# FTDIAdapter.net
KiCad netlist of a schematic drawn in EAGLE
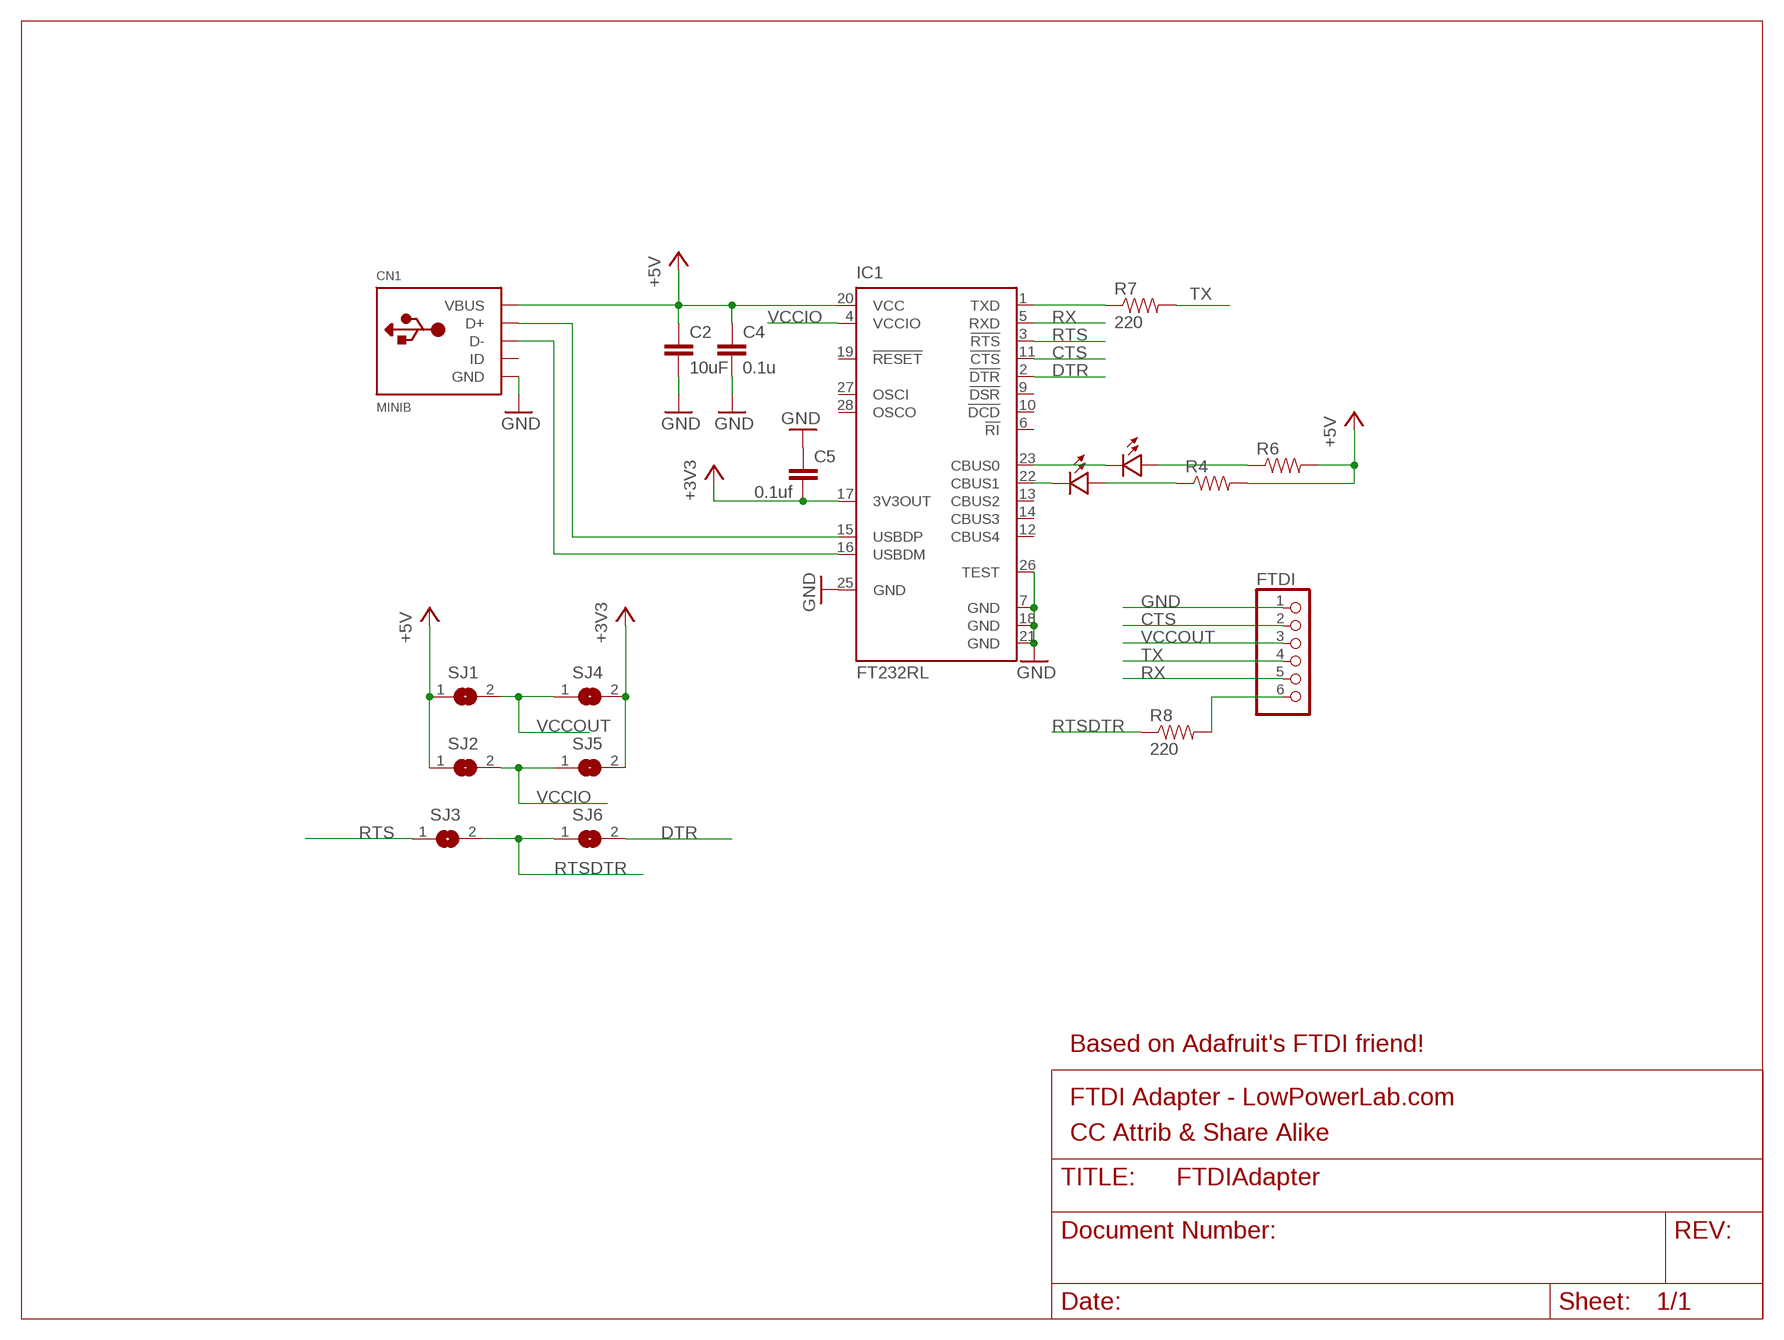
[diagram p0: schematic, sheet 1]

(export (version "E")
  (design (tool "Eeschema 10.0.6"))
  (components
    (comp (ref "C2")
      (value "10uF")
      (footprint "eagle-import:0805-CAP-LARGEPADS")
      (libsource (lib "eagle-import") (part "CAP0805-CAP-LARGEPADS"))
    )
    (comp (ref "C4")
      (value "0.1u")
      (footprint "eagle-import:0603-CAP")
      (libsource (lib "eagle-import") (part "CAP0603-CAP"))
    )
    (comp (ref "C5")
      (value "0.1uf")
      (footprint "eagle-import:0603-CAP")
      (libsource (lib "eagle-import") (part "CAP0603-CAP"))
    )
    (comp (ref "CN1")
      (value "MINIB")
      (footprint "eagle-import:USB-MINIB")
      (libsource (lib "eagle-import") (part "USBMINIB"))
    )
    (comp (ref "FTDI")
      (value "PINHD-1X6CB")
      (footprint "eagle-import:1X06-CLEANBIG")
      (libsource (lib "eagle-import") (part "PINHD-1X6CB"))
    )
    (comp (ref "IC1")
      (value "FT232RL")
      (footprint "eagle-import:SSOP28")
      (libsource (lib "eagle-import") (part "FT232RL"))
    )
    (comp (ref "R4")
      (value "RESISTOR0603-RES")
      (footprint "eagle-import:0603-RES")
      (libsource (lib "eagle-import") (part "RESISTOR0603-RES"))
    )
    (comp (ref "R6")
      (value "RESISTOR0603-RES")
      (footprint "eagle-import:0603-RES")
      (libsource (lib "eagle-import") (part "RESISTOR0603-RES"))
    )
    (comp (ref "R7")
      (value "220")
      (footprint "eagle-import:0603-RES")
      (libsource (lib "eagle-import") (part "RESISTOR0603-RES"))
    )
    (comp (ref "R8")
      (value "220")
      (footprint "eagle-import:0603-RES")
      (libsource (lib "eagle-import") (part "RESISTOR0603-RES"))
    )
    (comp (ref "SJ1") (value "SJ") (footprint "eagle-import:SJ") (libsource (lib "eagle-import") (part "SJ")))
    (comp (ref "SJ2") (value "SJ") (footprint "eagle-import:SJ") (libsource (lib "eagle-import") (part "SJ")))
    (comp (ref "SJ3") (value "SJ") (footprint "eagle-import:SJ") (libsource (lib "eagle-import") (part "SJ")))
    (comp (ref "SJ4") (value "SJ") (footprint "eagle-import:SJ") (libsource (lib "eagle-import") (part "SJ")))
    (comp (ref "SJ5") (value "SJ") (footprint "eagle-import:SJ") (libsource (lib "eagle-import") (part "SJ")))
    (comp (ref "SJ6") (value "SJ") (footprint "eagle-import:SJ") (libsource (lib "eagle-import") (part "SJ")))
    (comp (ref "U$4")
      (value "LED0603")
      (footprint "eagle-import:0603-LED")
      (libsource (lib "eagle-import") (part "LED0603"))
    )
    (comp (ref "U$5")
      (value "LED0603")
      (footprint "eagle-import:0603-LED")
      (libsource (lib "eagle-import") (part "LED0603"))
    )
  )
  (nets
    (net (code "1") (name "+3V3") (class "Default")
      (node (ref "C5") (pin "2") (pinfunction "2_2") (pintype "passive"))
      (node (ref "IC1") (pin "17") (pinfunction "3V3OUT_17") (pintype "input"))
      (node (ref "SJ4") (pin "2") (pinfunction "2_2") (pintype "passive"))
      (node (ref "SJ5") (pin "2") (pinfunction "2_2") (pintype "passive"))
    )
    (net (code "2") (name "+5V") (class "Default")
      (node (ref "C2") (pin "1") (pinfunction "1_1") (pintype "passive"))
      (node (ref "C4") (pin "1") (pinfunction "1_1") (pintype "passive"))
      (node (ref "CN1") (pin "VBUS") (pinfunction "VBUS_VBUS") (pintype "power_in"))
      (node (ref "IC1") (pin "20") (pinfunction "VCC_20") (pintype "input"))
      (node (ref "R4") (pin "2") (pinfunction "2_2") (pintype "passive"))
      (node (ref "R6") (pin "2") (pinfunction "2_2") (pintype "passive"))
      (node (ref "SJ1") (pin "1") (pinfunction "1_1") (pintype "passive"))
      (node (ref "SJ2") (pin "1") (pinfunction "1_1") (pintype "passive"))
    )
    (net (code "3") (name "/CTS") (class "Default")
      (node (ref "FTDI") (pin "2") (pinfunction "2_2") (pintype "passive"))
      (node (ref "IC1") (pin "11") (pinfunction "~{CTS}_11") (pintype "input"))
    )
    (net (code "4") (name "/DTR") (class "Default")
      (node (ref "IC1") (pin "2") (pinfunction "~{DTR}_2") (pintype "input"))
      (node (ref "SJ6") (pin "2") (pinfunction "2_2") (pintype "passive"))
    )
    (net (code "5") (name "/RTS") (class "Default")
      (node (ref "IC1") (pin "3") (pinfunction "~{RTS}_3") (pintype "input"))
      (node (ref "SJ3") (pin "1") (pinfunction "1_1") (pintype "passive"))
    )
    (net (code "6") (name "/RTSDTR") (class "Default")
      (node (ref "R8") (pin "1") (pinfunction "1_1") (pintype "passive"))
      (node (ref "SJ3") (pin "2") (pinfunction "2_2") (pintype "passive"))
      (node (ref "SJ6") (pin "1") (pinfunction "1_1") (pintype "passive"))
    )
    (net (code "7") (name "/RX") (class "Default")
      (node (ref "FTDI") (pin "5") (pinfunction "5_5") (pintype "passive"))
      (node (ref "IC1") (pin "5") (pinfunction "RXD_5") (pintype "input"))
    )
    (net (code "8") (name "/TX") (class "Default")
      (node (ref "FTDI") (pin "4") (pinfunction "4_4") (pintype "passive"))
      (node (ref "R7") (pin "2") (pinfunction "2_2") (pintype "passive"))
    )
    (net (code "9") (name "/VCCIO") (class "Default")
      (node (ref "IC1") (pin "4") (pinfunction "VCCIO_4") (pintype "input"))
      (node (ref "SJ2") (pin "2") (pinfunction "2_2") (pintype "passive"))
      (node (ref "SJ5") (pin "1") (pinfunction "1_1") (pintype "passive"))
    )
    (net (code "10") (name "/VCCOUT") (class "Default")
      (node (ref "FTDI") (pin "3") (pinfunction "3_3") (pintype "passive"))
      (node (ref "SJ1") (pin "2") (pinfunction "2_2") (pintype "passive"))
      (node (ref "SJ4") (pin "1") (pinfunction "1_1") (pintype "passive"))
    )
    (net (code "11") (name "GND") (class "Default")
      (node (ref "C2") (pin "2") (pinfunction "2_2") (pintype "passive"))
      (node (ref "C4") (pin "2") (pinfunction "2_2") (pintype "passive"))
      (node (ref "C5") (pin "1") (pinfunction "1_1") (pintype "passive"))
      (node (ref "CN1") (pin "GND") (pinfunction "GND_GND") (pintype "power_in"))
      (node (ref "FTDI") (pin "1") (pinfunction "1_1") (pintype "passive"))
      (node (ref "IC1") (pin "18") (pinfunction "GND_18") (pintype "input"))
      (node (ref "IC1") (pin "21") (pinfunction "GND_21") (pintype "input"))
      (node (ref "IC1") (pin "25") (pinfunction "GND_25") (pintype "input"))
      (node (ref "IC1") (pin "26") (pinfunction "TEST_26") (pintype "input"))
      (node (ref "IC1") (pin "7") (pinfunction "GND_7") (pintype "input"))
    )
    (net (code "12") (name "Net-(FTDI-Pad6)") (class "Default")
      (node (ref "FTDI") (pin "6") (pinfunction "6_6") (pintype "passive"))
      (node (ref "R8") (pin "2") (pinfunction "2_2") (pintype "passive"))
    )
    (net (code "13") (name "Net-(IC1-CBUS0)") (class "Default")
      (node (ref "IC1") (pin "23") (pinfunction "CBUS0_23") (pintype "input"))
      (node (ref "U$4") (pin "MINUS") (pinfunction "MINUS_MINUS") (pintype "passive"))
    )
    (net (code "14") (name "Net-(IC1-CBUS1)") (class "Default")
      (node (ref "IC1") (pin "22") (pinfunction "CBUS1_22") (pintype "input"))
      (node (ref "U$5") (pin "MINUS") (pinfunction "MINUS_MINUS") (pintype "passive"))
    )
    (net (code "15") (name "Net-(IC1-TXD)") (class "Default")
      (node (ref "IC1") (pin "1") (pinfunction "TXD_1") (pintype "input"))
      (node (ref "R7") (pin "1") (pinfunction "1_1") (pintype "passive"))
    )
    (net (code "16") (name "Net-(IC1-USBDM)") (class "Default")
      (node (ref "CN1") (pin "D-") (pinfunction "D-_D-") (pintype "bidirectional"))
      (node (ref "IC1") (pin "16") (pinfunction "USBDM_16") (pintype "input"))
    )
    (net (code "17") (name "Net-(IC1-USBDP)") (class "Default")
      (node (ref "CN1") (pin "D+") (pinfunction "D+_D+") (pintype "bidirectional"))
      (node (ref "IC1") (pin "15") (pinfunction "USBDP_15") (pintype "input"))
    )
    (net (code "18") (name "Net-(R4-Pad1)") (class "Default")
      (node (ref "R4") (pin "1") (pinfunction "1_1") (pintype "passive"))
      (node (ref "U$5") (pin "PLUS") (pinfunction "PLUS_PLUS") (pintype "passive"))
    )
    (net (code "19") (name "Net-(R6-Pad1)") (class "Default")
      (node (ref "R6") (pin "1") (pinfunction "1_1") (pintype "passive"))
      (node (ref "U$4") (pin "PLUS") (pinfunction "PLUS_PLUS") (pintype "passive"))
    )
    (net (code "20") (name "unconnected-(CN1-PadID)") (class "Default")
      (node (ref "CN1") (pin "ID") (pinfunction "ID_ID") (pintype "bidirectional"))
    )
    (net (code "21") (name "unconnected-(IC1-CBUS2-Pad13)") (class "Default")
      (node (ref "IC1") (pin "13") (pinfunction "CBUS2_13") (pintype "input"))
    )
    (net (code "22") (name "unconnected-(IC1-CBUS3-Pad14)") (class "Default")
      (node (ref "IC1") (pin "14") (pinfunction "CBUS3_14") (pintype "input"))
    )
    (net (code "23") (name "unconnected-(IC1-CBUS4-Pad12)") (class "Default")
      (node (ref "IC1") (pin "12") (pinfunction "CBUS4_12") (pintype "input"))
    )
    (net (code "24") (name "unconnected-(IC1-OSCI-Pad27)") (class "Default")
      (node (ref "IC1") (pin "27") (pinfunction "OSCI_27") (pintype "input"))
    )
    (net (code "25") (name "unconnected-(IC1-OSCO-Pad28)") (class "Default")
      (node (ref "IC1") (pin "28") (pinfunction "OSCO_28") (pintype "input"))
    )
    (net (code "26") (name "unconnected-(IC1-~{DCD}-Pad10)") (class "Default")
      (node (ref "IC1") (pin "10") (pinfunction "~{DCD}_10") (pintype "input"))
    )
    (net (code "27") (name "unconnected-(IC1-~{DSR}-Pad9)") (class "Default")
      (node (ref "IC1") (pin "9") (pinfunction "~{DSR}_9") (pintype "input"))
    )
    (net (code "28") (name "unconnected-(IC1-~{RESET}-Pad19)") (class "Default")
      (node (ref "IC1") (pin "19") (pinfunction "~{RESET}_19") (pintype "input"))
    )
    (net (code "29") (name "unconnected-(IC1-~{RI}-Pad6)") (class "Default")
      (node (ref "IC1") (pin "6") (pinfunction "~{RI}_6") (pintype "input"))
    )
  )
)
